# 4501-WB-AV-BMS-REV-A2-ISOSPI.net
KiCad netlist of a schematic drawn in Altium Designer
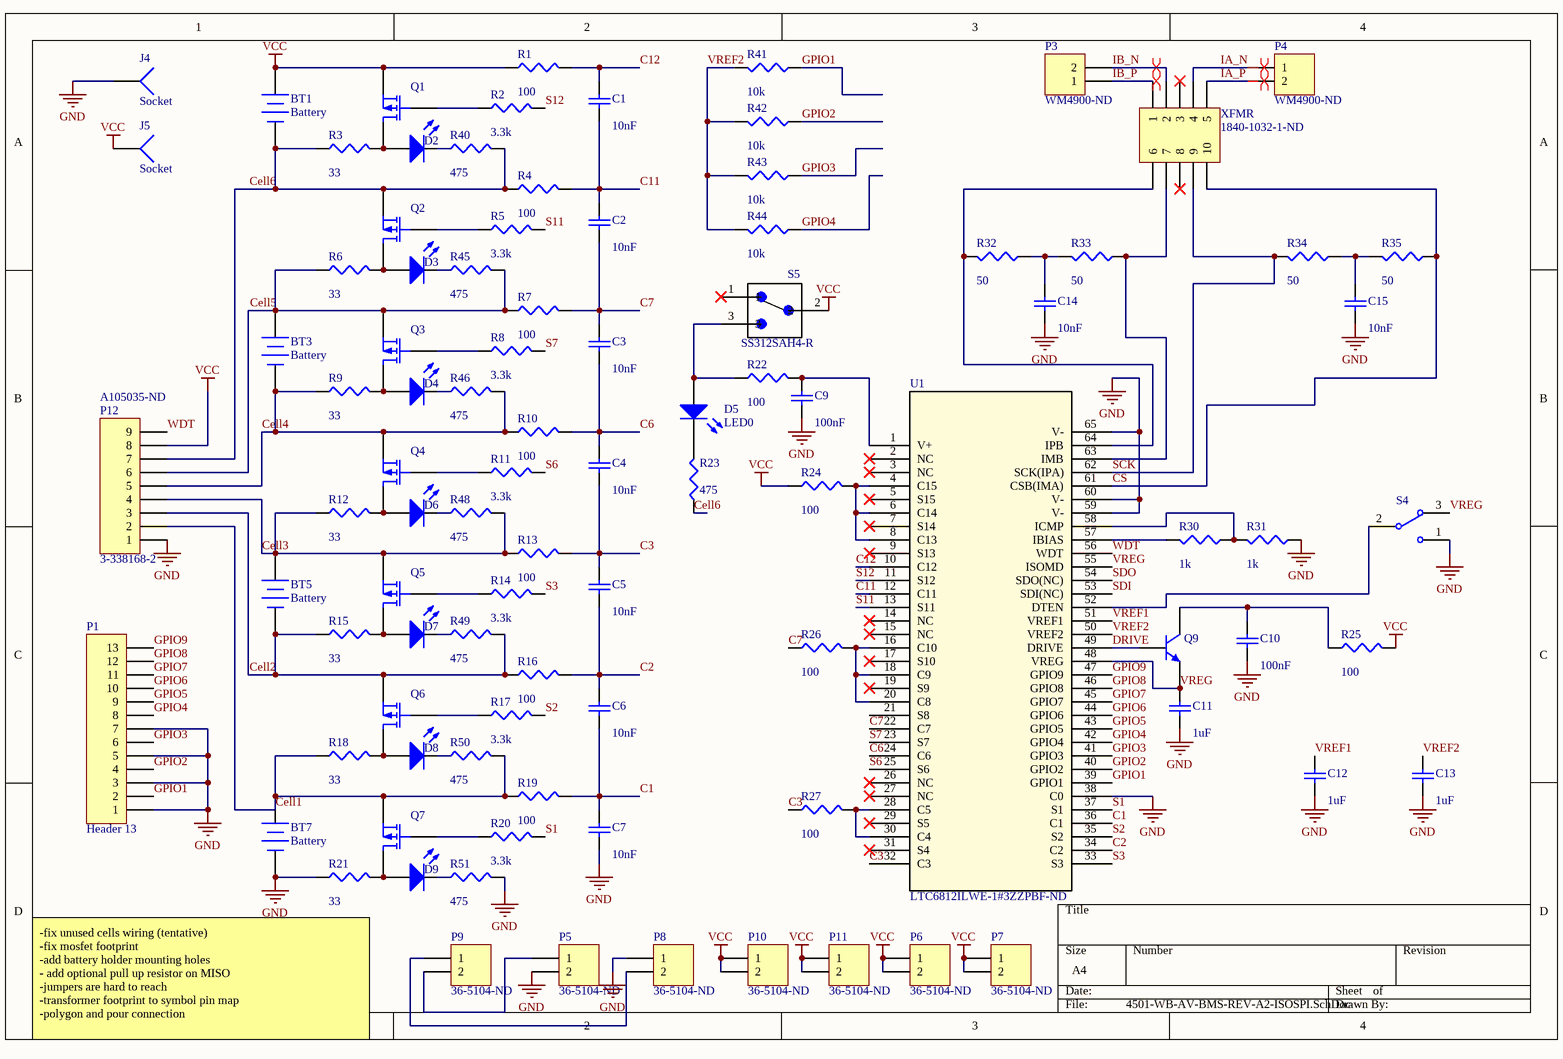
[diagram p0: 4501-WB-AV-BMS-REV-A2-ISOSPI.SchDoc]

(export (version "E")
  (design (tool "Eeschema 10.0.6"))
  (components
    (comp (ref "BT1")
      (value "Battery")
      (footprint "18650 SMD:PCBComponent_1")
      (description "Multicell Battery")
      (fields (field (name "PUBLISHER") "Altium Limited"))
      (libsource (lib "Miscellaneous Devices") (part "Battery"))
    )
    (comp (ref "BT3")
      (value "Battery")
      (footprint "18650 SMD:PCBComponent_1")
      (description "Multicell Battery")
      (fields (field (name "PUBLISHER") "Altium Limited"))
      (libsource (lib "Miscellaneous Devices") (part "Battery"))
    )
    (comp (ref "BT5")
      (value "Battery")
      (footprint "18650 SMD:PCBComponent_1")
      (description "Multicell Battery")
      (fields (field (name "PUBLISHER") "Altium Limited"))
      (libsource (lib "Miscellaneous Devices") (part "Battery"))
    )
    (comp (ref "BT7")
      (value "Battery")
      (footprint "18650 SMD:PCBComponent_1")
      (description "Multicell Battery")
      (fields (field (name "PUBLISHER") "Altium Limited"))
      (libsource (lib "Miscellaneous Devices") (part "Battery"))
    )
    (comp (ref "C1")
      (value "10nF")
      (footprint "1608[0603]")
      (description "Capacitor (Semiconductor SIM Model)")
      (fields (field (name "Comment") "399-1092-1-ND") (field (name "PUBLISHER") "Altium Limited"))
      (libsource (lib "Miscellaneous Devices") (part "Cap Semi"))
    )
    (comp (ref "C2")
      (value "10nF")
      (footprint "1608[0603]")
      (description "Capacitor (Semiconductor SIM Model)")
      (fields (field (name "Comment") "399-1092-1-ND") (field (name "PUBLISHER") "Altium Limited"))
      (libsource (lib "Miscellaneous Devices") (part "Cap Semi"))
    )
    (comp (ref "C3")
      (value "10nF")
      (footprint "1608[0603]")
      (description "Capacitor (Semiconductor SIM Model)")
      (fields (field (name "Comment") "399-1092-1-ND") (field (name "PUBLISHER") "Altium Limited"))
      (libsource (lib "Miscellaneous Devices") (part "Cap Semi"))
    )
    (comp (ref "C4")
      (value "10nF")
      (footprint "1608[0603]")
      (description "Capacitor (Semiconductor SIM Model)")
      (fields (field (name "Comment") "399-1092-1-ND") (field (name "PUBLISHER") "Altium Limited"))
      (libsource (lib "Miscellaneous Devices") (part "Cap Semi"))
    )
    (comp (ref "C5")
      (value "10nF")
      (footprint "1608[0603]")
      (description "Capacitor (Semiconductor SIM Model)")
      (fields (field (name "Comment") "399-1092-1-ND") (field (name "PUBLISHER") "Altium Limited"))
      (libsource (lib "Miscellaneous Devices") (part "Cap Semi"))
    )
    (comp (ref "C6")
      (value "10nF")
      (footprint "1608[0603]")
      (description "Capacitor (Semiconductor SIM Model)")
      (fields (field (name "Comment") "399-1092-1-ND") (field (name "PUBLISHER") "Altium Limited"))
      (libsource (lib "Miscellaneous Devices") (part "Cap Semi"))
    )
    (comp (ref "C7")
      (value "10nF")
      (footprint "1608[0603]")
      (description "Capacitor (Semiconductor SIM Model)")
      (fields (field (name "Comment") "399-1092-1-ND") (field (name "PUBLISHER") "Altium Limited"))
      (libsource (lib "Miscellaneous Devices") (part "Cap Semi"))
    )
    (comp (ref "C9")
      (value "100nF")
      (footprint "6-0805_N")
      (description "Capacitor (Semiconductor SIM Model)")
      (fields (field (name "Comment") "1276-1090-1-ND") (field (name "PUBLISHER") "Altium Limited"))
      (libsource (lib "Miscellaneous Devices") (part "Cap Semi"))
    )
    (comp (ref "C10")
      (value "100nF")
      (footprint "6-0805_N")
      (description "Capacitor (Semiconductor SIM Model)")
      (fields (field (name "Comment") "1276-1090-1-ND") (field (name "PUBLISHER") "Altium Limited"))
      (libsource (lib "Miscellaneous Devices") (part "Cap Semi"))
    )
    (comp (ref "C11")
      (value "1uF")
      (footprint "6-0805_N")
      (description "Capacitor (Semiconductor SIM Model)")
      (fields (field (name "Comment") "311-3498-1-ND") (field (name "PUBLISHER") "Altium Limited"))
      (libsource (lib "Miscellaneous Devices") (part "Cap Semi"))
    )
    (comp (ref "C12")
      (value "1uF")
      (footprint "6-0805_N")
      (description "Capacitor (Semiconductor SIM Model)")
      (fields (field (name "Comment") "311-3498-1-ND") (field (name "PUBLISHER") "Altium Limited"))
      (libsource (lib "Miscellaneous Devices") (part "Cap Semi"))
    )
    (comp (ref "C13")
      (value "1uF")
      (footprint "6-0805_N")
      (description "Capacitor (Semiconductor SIM Model)")
      (fields (field (name "Comment") "311-3498-1-ND") (field (name "PUBLISHER") "Altium Limited"))
      (libsource (lib "Miscellaneous Devices") (part "Cap Semi"))
    )
    (comp (ref "C14")
      (value "10nF")
      (footprint "1608[0603]")
      (description "Capacitor (Semiconductor SIM Model)")
      (fields (field (name "Comment") "399-1092-1-ND") (field (name "PUBLISHER") "Altium Limited"))
      (libsource (lib "Miscellaneous Devices") (part "Cap Semi"))
    )
    (comp (ref "C15")
      (value "10nF")
      (footprint "1608[0603]")
      (description "Capacitor (Semiconductor SIM Model)")
      (fields (field (name "Comment") "399-1092-1-ND") (field (name "PUBLISHER") "Altium Limited"))
      (libsource (lib "Miscellaneous Devices") (part "Cap Semi"))
    )
    (comp (ref "D2")
      (value "160-1435-1-ND")
      (footprint "J1-0603")
      (description "Typical INFRARED GaAs LED")
      (fields (field (name "PUBLISHER") "Altium Limited"))
      (libsource (lib "Miscellaneous Devices") (part "LED0"))
    )
    (comp (ref "D3")
      (value "160-1435-1-ND")
      (footprint "J1-0603")
      (description "Typical INFRARED GaAs LED")
      (fields (field (name "PUBLISHER") "Altium Limited"))
      (libsource (lib "Miscellaneous Devices") (part "LED0"))
    )
    (comp (ref "D4")
      (value "160-1435-1-ND")
      (footprint "J1-0603")
      (description "Typical INFRARED GaAs LED")
      (fields (field (name "PUBLISHER") "Altium Limited"))
      (libsource (lib "Miscellaneous Devices") (part "LED0"))
    )
    (comp (ref "D5")
      (value "LED0")
      (footprint "J1-0603")
      (description "Typical INFRARED GaAs LED")
      (fields (field (name "PUBLISHER") "Altium Limited"))
      (libsource (lib "Miscellaneous Devices") (part "LED0"))
    )
    (comp (ref "D6")
      (value "160-1435-1-ND")
      (footprint "J1-0603")
      (description "Typical INFRARED GaAs LED")
      (fields (field (name "PUBLISHER") "Altium Limited"))
      (libsource (lib "Miscellaneous Devices") (part "LED0"))
    )
    (comp (ref "D7")
      (value "160-1435-1-ND")
      (footprint "J1-0603")
      (description "Typical INFRARED GaAs LED")
      (fields (field (name "PUBLISHER") "Altium Limited"))
      (libsource (lib "Miscellaneous Devices") (part "LED0"))
    )
    (comp (ref "D8")
      (value "160-1435-1-ND")
      (footprint "J1-0603")
      (description "Typical INFRARED GaAs LED")
      (fields (field (name "PUBLISHER") "Altium Limited"))
      (libsource (lib "Miscellaneous Devices") (part "LED0"))
    )
    (comp (ref "D9")
      (value "160-1435-1-ND")
      (footprint "J1-0603")
      (description "Typical INFRARED GaAs LED")
      (fields (field (name "PUBLISHER") "Altium Limited"))
      (libsource (lib "Miscellaneous Devices") (part "LED0"))
    )
    (comp (ref "J4")
      (value "Socket")
      (footprint "SMD Power Pad:PCBComponent_1")
      (fields (field (name "PUBLISHER") "Altium Limited"))
      (libsource (lib "Miscellaneous Connectors") (part "Socket"))
    )
    (comp (ref "J5")
      (value "Socket")
      (footprint "SMD Power Pad:PCBComponent_1")
      (fields (field (name "PUBLISHER") "Altium Limited"))
      (libsource (lib "Miscellaneous Connectors") (part "Socket"))
    )
    (comp (ref "P1")
      (value "Header 13")
      (footprint "DIP10")
      (description "Header, 13-Pin")
      (fields (field (name "PUBLISHER") "Altium Limited"))
      (libsource (lib "Miscellaneous Connectors") (part "Header 13"))
    )
    (comp (ref "P3")
      (value "WM4900-ND")
      (footprint "Molex Connectors:WM4900-ND")
      (description "Header, 2-Pin")
      (fields (field (name "PUBLISHER") "Altium Limited"))
      (libsource (lib "Miscellaneous Connectors") (part "Header 2"))
    )
    (comp (ref "P4")
      (value "WM4900-ND")
      (footprint "Molex Connectors:WM4900-ND")
      (description "Header, 2-Pin")
      (fields (field (name "PUBLISHER") "Altium Limited"))
      (libsource (lib "") (part "Header 2_1"))
    )
    (comp (ref "P5")
      (value "36-5104-ND")
      (footprint "5104:PCBComponent_1")
      (description "Header, 2-Pin")
      (fields (field (name "PUBLISHER") "Altium Limited"))
      (libsource (lib "") (part "Header 2_1"))
    )
    (comp (ref "P6")
      (value "36-5104-ND")
      (footprint "5104:PCBComponent_1")
      (description "Header, 2-Pin")
      (fields (field (name "PUBLISHER") "Altium Limited"))
      (libsource (lib "") (part "Header 2_1"))
    )
    (comp (ref "P7")
      (value "36-5104-ND")
      (footprint "5104:PCBComponent_1")
      (description "Header, 2-Pin")
      (fields (field (name "PUBLISHER") "Altium Limited"))
      (libsource (lib "") (part "Header 2_1"))
    )
    (comp (ref "P8")
      (value "36-5104-ND")
      (footprint "5104:PCBComponent_1")
      (description "Header, 2-Pin")
      (fields (field (name "PUBLISHER") "Altium Limited"))
      (libsource (lib "") (part "Header 2_1"))
    )
    (comp (ref "P9")
      (value "36-5104-ND")
      (footprint "5104:PCBComponent_1")
      (description "Header, 2-Pin")
      (fields (field (name "PUBLISHER") "Altium Limited"))
      (libsource (lib "") (part "Header 2_1"))
    )
    (comp (ref "P10")
      (value "36-5104-ND")
      (footprint "5104:PCBComponent_1")
      (description "Header, 2-Pin")
      (fields (field (name "PUBLISHER") "Altium Limited"))
      (libsource (lib "") (part "Header 2_1"))
    )
    (comp (ref "P11")
      (value "36-5104-ND")
      (footprint "5104:PCBComponent_1")
      (description "Header, 2-Pin")
      (fields (field (name "PUBLISHER") "Altium Limited"))
      (libsource (lib "") (part "Header 2_1"))
    )
    (comp (ref "P12")
      (value "3-338168-2")
      (footprint "CONN_3-338168-2")
      (description "Header, 9-Pin")
      (fields
        (field (name "SUPPLIER PART NUMBER 1") "A105035-ND")
        (field (name "PUBLISHER") "Altium Limited")
      )
      (libsource (lib "Miscellaneous Connectors") (part "Header 9"))
    )
    (comp (ref "Q1")
      (value "BSS308PEH6327XTSA1CT-ND")
      (footprint "SOT95P245X110-3N")
      (description "P-Channel MOSFET")
      (fields (field (name "PUBLISHER") "Altium Limited"))
      (libsource (lib "Miscellaneous Devices") (part "MOSFET-P"))
    )
    (comp (ref "Q2")
      (value "BSS308PEH6327XTSA1CT-ND")
      (footprint "SOT95P245X110-3N")
      (description "P-Channel MOSFET")
      (fields (field (name "PUBLISHER") "Altium Limited"))
      (libsource (lib "Miscellaneous Devices") (part "MOSFET-P"))
    )
    (comp (ref "Q3")
      (value "BSS308PEH6327XTSA1CT-ND")
      (footprint "SOT95P245X110-3N")
      (description "P-Channel MOSFET")
      (fields (field (name "PUBLISHER") "Altium Limited"))
      (libsource (lib "Miscellaneous Devices") (part "MOSFET-P"))
    )
    (comp (ref "Q4")
      (value "BSS308PEH6327XTSA1CT-ND")
      (footprint "SOT95P245X110-3N")
      (description "P-Channel MOSFET")
      (fields (field (name "PUBLISHER") "Altium Limited"))
      (libsource (lib "Miscellaneous Devices") (part "MOSFET-P"))
    )
    (comp (ref "Q5")
      (value "BSS308PEH6327XTSA1CT-ND")
      (footprint "SOT95P245X110-3N")
      (description "P-Channel MOSFET")
      (fields (field (name "PUBLISHER") "Altium Limited"))
      (libsource (lib "Miscellaneous Devices") (part "MOSFET-P"))
    )
    (comp (ref "Q6")
      (value "BSS308PEH6327XTSA1CT-ND")
      (footprint "SOT95P245X110-3N")
      (description "P-Channel MOSFET")
      (fields (field (name "PUBLISHER") "Altium Limited"))
      (libsource (lib "Miscellaneous Devices") (part "MOSFET-P"))
    )
    (comp (ref "Q7")
      (value "BSS308PEH6327XTSA1CT-ND")
      (footprint "SOT95P245X110-3N")
      (description "P-Channel MOSFET")
      (fields (field (name "PUBLISHER") "Altium Limited"))
      (libsource (lib "Miscellaneous Devices") (part "MOSFET-P"))
    )
    (comp (ref "Q9")
      (value "DXT5551P5-13CT-ND")
      (footprint "DXT5551P5-13")
      (description "NPN General Purpose Amplifier")
      (fields (field (name "PUBLISHER") "Altium Limited"))
      (libsource (lib "Miscellaneous Devices") (part "2N3904"))
    )
    (comp (ref "R1")
      (value "100")
      (footprint "J1-0603")
      (description "Resistor")
      (fields (field (name "Comment") "A129676CT-ND") (field (name "PUBLISHER") "Altium Limited"))
      (libsource (lib "Miscellaneous Devices") (part "Res3"))
    )
    (comp (ref "R2")
      (value "3.3k")
      (footprint "J1-0603")
      (description "Resistor")
      (fields (field (name "Comment") "A129543CT-ND") (field (name "PUBLISHER") "Altium Limited"))
      (libsource (lib "Miscellaneous Devices") (part "Res3"))
    )
    (comp (ref "R3")
      (value "33")
      (footprint "12Z-2010")
      (description "Resistor")
      (fields (field (name "Comment") "A130642CT-ND") (field (name "PUBLISHER") "Altium Limited"))
      (libsource (lib "Miscellaneous Devices") (part "Res3"))
    )
    (comp (ref "R4")
      (value "100")
      (footprint "J1-0603")
      (description "Resistor")
      (fields (field (name "Comment") "A129676CT-ND") (field (name "PUBLISHER") "Altium Limited"))
      (libsource (lib "Miscellaneous Devices") (part "Res3"))
    )
    (comp (ref "R5")
      (value "3.3k")
      (footprint "J1-0603")
      (description "Resistor")
      (fields (field (name "Comment") "A129543CT-ND") (field (name "PUBLISHER") "Altium Limited"))
      (libsource (lib "Miscellaneous Devices") (part "Res3"))
    )
    (comp (ref "R6")
      (value "33")
      (footprint "12Z-2010")
      (description "Resistor")
      (fields (field (name "Comment") "A130642CT-ND") (field (name "PUBLISHER") "Altium Limited"))
      (libsource (lib "Miscellaneous Devices") (part "Res3"))
    )
    (comp (ref "R7")
      (value "100")
      (footprint "J1-0603")
      (description "Resistor")
      (fields (field (name "Comment") "A129676CT-ND") (field (name "PUBLISHER") "Altium Limited"))
      (libsource (lib "Miscellaneous Devices") (part "Res3"))
    )
    (comp (ref "R8")
      (value "3.3k")
      (footprint "J1-0603")
      (description "Resistor")
      (fields (field (name "Comment") "A129543CT-ND") (field (name "PUBLISHER") "Altium Limited"))
      (libsource (lib "Miscellaneous Devices") (part "Res3"))
    )
    (comp (ref "R9")
      (value "33")
      (footprint "12Z-2010")
      (description "Resistor")
      (fields (field (name "Comment") "A130642CT-ND") (field (name "PUBLISHER") "Altium Limited"))
      (libsource (lib "Miscellaneous Devices") (part "Res3"))
    )
    (comp (ref "R10")
      (value "100")
      (footprint "J1-0603")
      (description "Resistor")
      (fields (field (name "Comment") "A129676CT-ND") (field (name "PUBLISHER") "Altium Limited"))
      (libsource (lib "Miscellaneous Devices") (part "Res3"))
    )
    (comp (ref "R11")
      (value "3.3k")
      (footprint "J1-0603")
      (description "Resistor")
      (fields (field (name "Comment") "A129543CT-ND") (field (name "PUBLISHER") "Altium Limited"))
      (libsource (lib "Miscellaneous Devices") (part "Res3"))
    )
    (comp (ref "R12")
      (value "33")
      (footprint "12Z-2010")
      (description "Resistor")
      (fields (field (name "Comment") "A130642CT-ND") (field (name "PUBLISHER") "Altium Limited"))
      (libsource (lib "Miscellaneous Devices") (part "Res3"))
    )
    (comp (ref "R13")
      (value "100")
      (footprint "J1-0603")
      (description "Resistor")
      (fields (field (name "Comment") "A129676CT-ND") (field (name "PUBLISHER") "Altium Limited"))
      (libsource (lib "Miscellaneous Devices") (part "Res3"))
    )
    (comp (ref "R14")
      (value "3.3k")
      (footprint "J1-0603")
      (description "Resistor")
      (fields (field (name "Comment") "A129543CT-ND") (field (name "PUBLISHER") "Altium Limited"))
      (libsource (lib "Miscellaneous Devices") (part "Res3"))
    )
    (comp (ref "R15")
      (value "33")
      (footprint "12Z-2010")
      (description "Resistor")
      (fields (field (name "Comment") "A130642CT-ND") (field (name "PUBLISHER") "Altium Limited"))
      (libsource (lib "Miscellaneous Devices") (part "Res3"))
    )
    (comp (ref "R16")
      (value "100")
      (footprint "J1-0603")
      (description "Resistor")
      (fields (field (name "Comment") "A129676CT-ND") (field (name "PUBLISHER") "Altium Limited"))
      (libsource (lib "Miscellaneous Devices") (part "Res3"))
    )
    (comp (ref "R17")
      (value "3.3k")
      (footprint "J1-0603")
      (description "Resistor")
      (fields (field (name "Comment") "A129543CT-ND") (field (name "PUBLISHER") "Altium Limited"))
      (libsource (lib "Miscellaneous Devices") (part "Res3"))
    )
    (comp (ref "R18")
      (value "33")
      (footprint "12Z-2010")
      (description "Resistor")
      (fields (field (name "Comment") "A130642CT-ND") (field (name "PUBLISHER") "Altium Limited"))
      (libsource (lib "Miscellaneous Devices") (part "Res3"))
    )
    (comp (ref "R19")
      (value "100")
      (footprint "J1-0603")
      (description "Resistor")
      (fields (field (name "Comment") "A129676CT-ND") (field (name "PUBLISHER") "Altium Limited"))
      (libsource (lib "Miscellaneous Devices") (part "Res3"))
    )
    (comp (ref "R20")
      (value "3.3k")
      (footprint "J1-0603")
      (description "Resistor")
      (fields (field (name "Comment") "A129543CT-ND") (field (name "PUBLISHER") "Altium Limited"))
      (libsource (lib "Miscellaneous Devices") (part "Res3"))
    )
    (comp (ref "R21")
      (value "33")
      (footprint "12Z-2010")
      (description "Resistor")
      (fields (field (name "Comment") "A130642CT-ND") (field (name "PUBLISHER") "Altium Limited"))
      (libsource (lib "Miscellaneous Devices") (part "Res3"))
    )
    (comp (ref "R22")
      (value "100")
      (footprint "J1-0603")
      (description "Resistor")
      (fields (field (name "Comment") "A129676CT-ND") (field (name "PUBLISHER") "Altium Limited"))
      (libsource (lib "Miscellaneous Devices") (part "Res3"))
    )
    (comp (ref "R23")
      (value "475")
      (footprint "J1-0603")
      (description "Resistor")
      (fields (field (name "Comment") "RMCF2010JT33R0CT-ND") (field (name "PUBLISHER") "Altium Limited"))
      (libsource (lib "Miscellaneous Devices") (part "Res3"))
    )
    (comp (ref "R24")
      (value "100")
      (footprint "J1-0603")
      (description "Resistor")
      (fields (field (name "Comment") "A129676CT-ND") (field (name "PUBLISHER") "Altium Limited"))
      (libsource (lib "Miscellaneous Devices") (part "Res3"))
    )
    (comp (ref "R25")
      (value "100")
      (footprint "J1-0603")
      (description "Resistor")
      (fields (field (name "Comment") "A129676CT-ND") (field (name "PUBLISHER") "Altium Limited"))
      (libsource (lib "Miscellaneous Devices") (part "Res3"))
    )
    (comp (ref "R26")
      (value "100")
      (footprint "J1-0603")
      (description "Resistor")
      (fields (field (name "Comment") "A129676CT-ND") (field (name "PUBLISHER") "Altium Limited"))
      (libsource (lib "Miscellaneous Devices") (part "Res3"))
    )
    (comp (ref "R27")
      (value "100")
      (footprint "J1-0603")
      (description "Resistor")
      (fields (field (name "Comment") "A129676CT-ND") (field (name "PUBLISHER") "Altium Limited"))
      (libsource (lib "Miscellaneous Devices") (part "Res3"))
    )
    (comp (ref "R30")
      (value "1k")
      (footprint "J1-0603")
      (description "Resistor")
      (fields (field (name "Comment") "RNCP0603FTD1K00CT-ND") (field (name "PUBLISHER") "Altium Limited"))
      (libsource (lib "Miscellaneous Devices") (part "Res3"))
    )
    (comp (ref "R31")
      (value "1k")
      (footprint "J1-0603")
      (description "Resistor")
      (fields (field (name "Comment") "RNCP0603FTD1K00CT-ND") (field (name "PUBLISHER") "Altium Limited"))
      (libsource (lib "Miscellaneous Devices") (part "Res3"))
    )
    (comp (ref "R32")
      (value "50")
      (footprint "J1-0603")
      (description "Resistor")
      (fields (field (name "Comment") "311-2598-1-ND") (field (name "PUBLISHER") "Altium Limited"))
      (libsource (lib "Miscellaneous Devices") (part "Res3"))
    )
    (comp (ref "R33")
      (value "50")
      (footprint "J1-0603")
      (description "Resistor")
      (fields (field (name "Comment") "311-2598-1-ND") (field (name "PUBLISHER") "Altium Limited"))
      (libsource (lib "Miscellaneous Devices") (part "Res3"))
    )
    (comp (ref "R34")
      (value "50")
      (footprint "J1-0603")
      (description "Resistor")
      (fields (field (name "Comment") "311-2598-1-ND") (field (name "PUBLISHER") "Altium Limited"))
      (libsource (lib "Miscellaneous Devices") (part "Res3"))
    )
    (comp (ref "R35")
      (value "50")
      (footprint "J1-0603")
      (description "Resistor")
      (fields (field (name "Comment") "311-2598-1-ND") (field (name "PUBLISHER") "Altium Limited"))
      (libsource (lib "Miscellaneous Devices") (part "Res3"))
    )
    (comp (ref "R40")
      (value "475")
      (footprint "J1-0603")
      (description "Resistor")
      (fields (field (name "Comment") "RMCF2010JT33R0CT-ND") (field (name "PUBLISHER") "Altium Limited"))
      (libsource (lib "Miscellaneous Devices") (part "Res3"))
    )
    (comp (ref "R41")
      (value "10k")
      (footprint "J1-0603")
      (description "Resistor")
      (fields (field (name "Comment") "RNCP0603FTD10K0CT-ND") (field (name "PUBLISHER") "Altium Limited"))
      (libsource (lib "Miscellaneous Devices") (part "Res3"))
    )
    (comp (ref "R42")
      (value "10k")
      (footprint "J1-0603")
      (description "Resistor")
      (fields (field (name "Comment") "RNCP0603FTD10K0CT-ND") (field (name "PUBLISHER") "Altium Limited"))
      (libsource (lib "Miscellaneous Devices") (part "Res3"))
    )
    (comp (ref "R43")
      (value "10k")
      (footprint "J1-0603")
      (description "Resistor")
      (fields (field (name "Comment") "RNCP0603FTD10K0CT-ND") (field (name "PUBLISHER") "Altium Limited"))
      (libsource (lib "Miscellaneous Devices") (part "Res3"))
    )
    (comp (ref "R44")
      (value "10k")
      (footprint "J1-0603")
      (description "Resistor")
      (fields (field (name "Comment") "RNCP0603FTD10K0CT-ND") (field (name "PUBLISHER") "Altium Limited"))
      (libsource (lib "Miscellaneous Devices") (part "Res3"))
    )
    (comp (ref "R45")
      (value "475")
      (footprint "J1-0603")
      (description "Resistor")
      (fields (field (name "Comment") "RMCF2010JT33R0CT-ND") (field (name "PUBLISHER") "Altium Limited"))
      (libsource (lib "Miscellaneous Devices") (part "Res3"))
    )
    (comp (ref "R46")
      (value "475")
      (footprint "J1-0603")
      (description "Resistor")
      (fields (field (name "Comment") "RMCF2010JT33R0CT-ND") (field (name "PUBLISHER") "Altium Limited"))
      (libsource (lib "Miscellaneous Devices") (part "Res3"))
    )
    (comp (ref "R48")
      (value "475")
      (footprint "J1-0603")
      (description "Resistor")
      (fields (field (name "Comment") "RMCF2010JT33R0CT-ND") (field (name "PUBLISHER") "Altium Limited"))
      (libsource (lib "Miscellaneous Devices") (part "Res3"))
    )
    (comp (ref "R49")
      (value "475")
      (footprint "J1-0603")
      (description "Resistor")
      (fields (field (name "Comment") "RMCF2010JT33R0CT-ND") (field (name "PUBLISHER") "Altium Limited"))
      (libsource (lib "Miscellaneous Devices") (part "Res3"))
    )
    (comp (ref "R50")
      (value "475")
      (footprint "J1-0603")
      (description "Resistor")
      (fields (field (name "Comment") "RMCF2010JT33R0CT-ND") (field (name "PUBLISHER") "Altium Limited"))
      (libsource (lib "Miscellaneous Devices") (part "Res3"))
    )
    (comp (ref "R51")
      (value "475")
      (footprint "J1-0603")
      (description "Resistor")
      (fields (field (name "Comment") "RMCF2010JT33R0CT-ND") (field (name "PUBLISHER") "Altium Limited"))
      (libsource (lib "Miscellaneous Devices") (part "Res3"))
    )
    (comp (ref "S4")
      (value "S9337-ND, SAM8981-ND")
      (footprint "*TSM-103-01-L-SV")
      (description "SPDT Subminiature Toggle Switch, Right Angle Mounting, Vertical Actuation")
      (fields (field (name "PUBLISHER") "Altium Limited"))
      (libsource (lib "Miscellaneous Devices") (part "SW-SPDT"))
    )
    (comp (ref "S5")
      (value "SS312SAH4-R")
      (footprint "*SW_SS312SAH4-R")
      (description "Switch Slide ON None ON SPDT Side Slide 0.1A 28VAC 28VDC 0.4VA 10000Cycles Gull Wing SMD T/R")
      (fields (field (name "MF") "NKK Switches"))
      (libsource (lib "SS312SAH4-R") (part "SS312SAH4-R"))
    )
    (comp (ref "U1")
      (value "LTC6812ILWE-1#3ZZPBF-ND")
      (footprint "LQFP64_LWE_A - duplicate")
      (description "No Description Available")
      (fields (field (name "COPYRIGHT") "Copyright (C) 2018 Accelerated Designs. All rights reserved"))
      (libsource (lib "LTC6812") (part "LTC6812HLWE-1"))
    )
    (comp (ref "XFMR")
      (value "1840-1032-1-ND")
      (footprint "HM2100NLT")
      (description "Header, 5-Pin, Dual row\r\nHM2100NLT")
      (fields (field (name "PUBLISHER") "Altium Limited"))
      (libsource (lib "Miscellaneous Connectors") (part "Header 5X2A"))
    )
  )
  (nets
    (net (code "1") (name "/C1") (class "Default")
      (node (ref "C6") (pin "1") (pinfunction "1_1") (pintype "passive"))
      (node (ref "C7") (pin "2") (pinfunction "2_2") (pintype "passive"))
      (node (ref "R19") (pin "2") (pinfunction "2_2") (pintype "passive"))
      (node (ref "U1") (pin "36") (pinfunction "C1_36") (pintype "passive"))
    )
    (net (code "2") (name "/C2") (class "Default")
      (node (ref "C5") (pin "1") (pinfunction "1_1") (pintype "passive"))
      (node (ref "C6") (pin "2") (pinfunction "2_2") (pintype "passive"))
      (node (ref "R16") (pin "2") (pinfunction "2_2") (pintype "passive"))
      (node (ref "U1") (pin "34") (pinfunction "C2_34") (pintype "passive"))
    )
    (net (code "3") (name "/C3") (class "Default")
      (node (ref "C4") (pin "1") (pinfunction "1_1") (pintype "passive"))
      (node (ref "C5") (pin "2") (pinfunction "2_2") (pintype "passive"))
      (node (ref "R13") (pin "2") (pinfunction "2_2") (pintype "passive"))
      (node (ref "R27") (pin "1") (pinfunction "1_1") (pintype "passive"))
      (node (ref "U1") (pin "32") (pinfunction "C3_32") (pintype "passive"))
    )
    (net (code "4") (name "/C6") (class "Default")
      (node (ref "C3") (pin "1") (pinfunction "1_1") (pintype "passive"))
      (node (ref "C4") (pin "2") (pinfunction "2_2") (pintype "passive"))
      (node (ref "R10") (pin "2") (pinfunction "2_2") (pintype "passive"))
      (node (ref "U1") (pin "24") (pinfunction "C6_24") (pintype "passive"))
    )
    (net (code "5") (name "/C7") (class "Default")
      (node (ref "C2") (pin "1") (pinfunction "1_1") (pintype "passive"))
      (node (ref "C3") (pin "2") (pinfunction "2_2") (pintype "passive"))
      (node (ref "R26") (pin "1") (pinfunction "1_1") (pintype "passive"))
      (node (ref "R7") (pin "2") (pinfunction "2_2") (pintype "passive"))
      (node (ref "U1") (pin "22") (pinfunction "C7_22") (pintype "passive"))
    )
    (net (code "6") (name "/C11") (class "Default")
      (node (ref "C1") (pin "1") (pinfunction "1_1") (pintype "passive"))
      (node (ref "C2") (pin "2") (pinfunction "2_2") (pintype "passive"))
      (node (ref "R4") (pin "2") (pinfunction "2_2") (pintype "passive"))
      (node (ref "U1") (pin "12") (pinfunction "C11_12") (pintype "passive"))
    )
    (net (code "7") (name "/C12") (class "Default")
      (node (ref "C1") (pin "2") (pinfunction "2_2") (pintype "passive"))
      (node (ref "R1") (pin "2") (pinfunction "2_2") (pintype "passive"))
      (node (ref "U1") (pin "10") (pinfunction "C12_10") (pintype "passive"))
    )
    (net (code "8") (name "/CS") (class "Default")
      (node (ref "R35") (pin "2") (pinfunction "2_2") (pintype "passive"))
      (node (ref "U1") (pin "61") (pinfunction "CSB(IMA)_61") (pintype "passive"))
      (node (ref "XFMR") (pin "10") (pinfunction "10_10") (pintype "passive"))
    )
    (net (code "9") (name "/Cell1") (class "Default")
      (node (ref "BT7") (pin "1") (pinfunction "+_1") (pintype "passive"))
      (node (ref "P12") (pin "2") (pinfunction "2_2") (pintype "passive"))
      (node (ref "Q7") (pin "3") (pinfunction "S_3") (pintype "passive"))
      (node (ref "R18") (pin "2") (pinfunction "2_2") (pintype "passive"))
      (node (ref "R19") (pin "1") (pinfunction "1_1") (pintype "passive"))
      (node (ref "R50") (pin "1") (pinfunction "1_1") (pintype "passive"))
    )
    (net (code "10") (name "/Cell2") (class "Default")
      (node (ref "BT5") (pin "2") (pinfunction "-_2") (pintype "passive"))
      (node (ref "P12") (pin "3") (pinfunction "3_3") (pintype "passive"))
      (node (ref "Q6") (pin "3") (pinfunction "S_3") (pintype "passive"))
      (node (ref "R15") (pin "2") (pinfunction "2_2") (pintype "passive"))
      (node (ref "R16") (pin "1") (pinfunction "1_1") (pintype "passive"))
      (node (ref "R49") (pin "1") (pinfunction "1_1") (pintype "passive"))
    )
    (net (code "11") (name "/Cell3") (class "Default")
      (node (ref "BT5") (pin "1") (pinfunction "+_1") (pintype "passive"))
      (node (ref "P12") (pin "4") (pinfunction "4_4") (pintype "passive"))
      (node (ref "Q5") (pin "3") (pinfunction "S_3") (pintype "passive"))
      (node (ref "R12") (pin "2") (pinfunction "2_2") (pintype "passive"))
      (node (ref "R13") (pin "1") (pinfunction "1_1") (pintype "passive"))
      (node (ref "R48") (pin "1") (pinfunction "1_1") (pintype "passive"))
    )
    (net (code "12") (name "/Cell4") (class "Default")
      (node (ref "BT3") (pin "2") (pinfunction "-_2") (pintype "passive"))
      (node (ref "P12") (pin "5") (pinfunction "5_5") (pintype "passive"))
      (node (ref "Q4") (pin "3") (pinfunction "S_3") (pintype "passive"))
      (node (ref "R10") (pin "1") (pinfunction "1_1") (pintype "passive"))
      (node (ref "R46") (pin "1") (pinfunction "1_1") (pintype "passive"))
      (node (ref "R9") (pin "2") (pinfunction "2_2") (pintype "passive"))
    )
    (net (code "13") (name "/Cell5") (class "Default")
      (node (ref "BT3") (pin "1") (pinfunction "+_1") (pintype "passive"))
      (node (ref "P12") (pin "6") (pinfunction "6_6") (pintype "passive"))
      (node (ref "Q3") (pin "3") (pinfunction "S_3") (pintype "passive"))
      (node (ref "R45") (pin "1") (pinfunction "1_1") (pintype "passive"))
      (node (ref "R6") (pin "2") (pinfunction "2_2") (pintype "passive"))
      (node (ref "R7") (pin "1") (pinfunction "1_1") (pintype "passive"))
    )
    (net (code "14") (name "/Cell6") (class "Default")
      (node (ref "BT1") (pin "2") (pinfunction "-_2") (pintype "passive"))
      (node (ref "P12") (pin "7") (pinfunction "7_7") (pintype "passive"))
      (node (ref "Q2") (pin "3") (pinfunction "S_3") (pintype "passive"))
      (node (ref "R23") (pin "2") (pinfunction "2_2") (pintype "passive"))
      (node (ref "R3") (pin "2") (pinfunction "2_2") (pintype "passive"))
      (node (ref "R4") (pin "1") (pinfunction "1_1") (pintype "passive"))
      (node (ref "R40") (pin "1") (pinfunction "1_1") (pintype "passive"))
    )
    (net (code "15") (name "/DRIVE") (class "Default")
      (node (ref "Q9") (pin "2") (pinfunction "B_2") (pintype "passive"))
      (node (ref "U1") (pin "49") (pinfunction "DRIVE_49") (pintype "passive"))
    )
    (net (code "16") (name "/GPIO1") (class "Default")
      (node (ref "P1") (pin "2") (pinfunction "2_2") (pintype "passive"))
      (node (ref "R41") (pin "2") (pinfunction "2_2") (pintype "passive"))
      (node (ref "U1") (pin "39") (pinfunction "GPIO1_39") (pintype "passive"))
    )
    (net (code "17") (name "/GPIO2") (class "Default")
      (node (ref "P1") (pin "4") (pinfunction "4_4") (pintype "passive"))
      (node (ref "R42") (pin "2") (pinfunction "2_2") (pintype "passive"))
      (node (ref "U1") (pin "40") (pinfunction "GPIO2_40") (pintype "passive"))
    )
    (net (code "18") (name "/GPIO3") (class "Default")
      (node (ref "P1") (pin "6") (pinfunction "6_6") (pintype "passive"))
      (node (ref "R43") (pin "2") (pinfunction "2_2") (pintype "passive"))
      (node (ref "U1") (pin "41") (pinfunction "GPIO3_41") (pintype "passive"))
    )
    (net (code "19") (name "/GPIO4") (class "Default")
      (node (ref "P1") (pin "8") (pinfunction "8_8") (pintype "passive"))
      (node (ref "R44") (pin "2") (pinfunction "2_2") (pintype "passive"))
      (node (ref "U1") (pin "42") (pinfunction "GPIO4_42") (pintype "passive"))
    )
    (net (code "20") (name "/GPIO5") (class "Default")
      (node (ref "P1") (pin "9") (pinfunction "9_9") (pintype "passive"))
      (node (ref "U1") (pin "43") (pinfunction "GPIO5_43") (pintype "passive"))
    )
    (net (code "21") (name "/GPIO6") (class "Default")
      (node (ref "P1") (pin "10") (pinfunction "10_10") (pintype "passive"))
      (node (ref "U1") (pin "44") (pinfunction "GPIO6_44") (pintype "passive"))
    )
    (net (code "22") (name "/GPIO7") (class "Default")
      (node (ref "P1") (pin "11") (pinfunction "11_11") (pintype "passive"))
      (node (ref "U1") (pin "45") (pinfunction "GPIO7_45") (pintype "passive"))
    )
    (net (code "23") (name "/GPIO8") (class "Default")
      (node (ref "P1") (pin "12") (pinfunction "12_12") (pintype "passive"))
      (node (ref "U1") (pin "46") (pinfunction "GPIO8_46") (pintype "passive"))
    )
    (net (code "24") (name "/GPIO9") (class "Default")
      (node (ref "P1") (pin "13") (pinfunction "13_13") (pintype "passive"))
      (node (ref "U1") (pin "47") (pinfunction "GPIO9_47") (pintype "passive"))
    )
    (net (code "25") (name "/IA_N") (class "Default")
      (node (ref "P4") (pin "1") (pinfunction "1_1") (pintype "passive"))
      (node (ref "XFMR") (pin "4") (pinfunction "4_4") (pintype "passive"))
    )
    (net (code "26") (name "/IA_P") (class "Default")
      (node (ref "P4") (pin "2") (pinfunction "2_2") (pintype "passive"))
      (node (ref "XFMR") (pin "5") (pinfunction "5_5") (pintype "passive"))
    )
    (net (code "27") (name "/IB_N") (class "Default")
      (node (ref "P3") (pin "2") (pinfunction "2_2") (pintype "passive"))
      (node (ref "XFMR") (pin "2") (pinfunction "2_2") (pintype "passive"))
    )
    (net (code "28") (name "/IB_P") (class "Default")
      (node (ref "P3") (pin "1") (pinfunction "1_1") (pintype "passive"))
      (node (ref "XFMR") (pin "1") (pinfunction "1_1") (pintype "passive"))
    )
    (net (code "29") (name "/S1") (class "Default")
      (node (ref "R20") (pin "2") (pinfunction "2_2") (pintype "passive"))
      (node (ref "U1") (pin "37") (pinfunction "S1_37") (pintype "passive"))
    )
    (net (code "30") (name "/S2") (class "Default")
      (node (ref "R17") (pin "2") (pinfunction "2_2") (pintype "passive"))
      (node (ref "U1") (pin "35") (pinfunction "S2_35") (pintype "passive"))
    )
    (net (code "31") (name "/S3") (class "Default")
      (node (ref "R14") (pin "2") (pinfunction "2_2") (pintype "passive"))
      (node (ref "U1") (pin "33") (pinfunction "S3_33") (pintype "passive"))
    )
    (net (code "32") (name "/S6") (class "Default")
      (node (ref "R11") (pin "2") (pinfunction "2_2") (pintype "passive"))
      (node (ref "U1") (pin "25") (pinfunction "S6_25") (pintype "passive"))
    )
    (net (code "33") (name "/S7") (class "Default")
      (node (ref "R8") (pin "2") (pinfunction "2_2") (pintype "passive"))
      (node (ref "U1") (pin "23") (pinfunction "S7_23") (pintype "passive"))
    )
    (net (code "34") (name "/S11") (class "Default")
      (node (ref "R5") (pin "2") (pinfunction "2_2") (pintype "passive"))
      (node (ref "U1") (pin "13") (pinfunction "S11_13") (pintype "passive"))
    )
    (net (code "35") (name "/S12") (class "Default")
      (node (ref "R2") (pin "2") (pinfunction "2_2") (pintype "passive"))
      (node (ref "U1") (pin "11") (pinfunction "S12_11") (pintype "passive"))
    )
    (net (code "36") (name "/SCK") (class "Default")
      (node (ref "R34") (pin "1") (pinfunction "1_1") (pintype "passive"))
      (node (ref "U1") (pin "62") (pinfunction "SCK(IPA)_62") (pintype "passive"))
      (node (ref "XFMR") (pin "9") (pinfunction "9_9") (pintype "passive"))
    )
    (net (code "37") (name "/SDI") (class "Default")
      (node (ref "U1") (pin "53") (pinfunction "SDI(NC)_53") (pintype "passive"))
    )
    (net (code "38") (name "/SDO") (class "Default")
      (node (ref "U1") (pin "54") (pinfunction "SDO(NC)_54") (pintype "passive"))
    )
    (net (code "39") (name "/VREF1") (class "Default")
      (node (ref "C12") (pin "2") (pinfunction "2_2") (pintype "passive"))
      (node (ref "U1") (pin "51") (pinfunction "VREF1_51") (pintype "passive"))
    )
    (net (code "40") (name "/VREF2") (class "Default")
      (node (ref "C13") (pin "2") (pinfunction "2_2") (pintype "passive"))
      (node (ref "R41") (pin "1") (pinfunction "1_1") (pintype "passive"))
      (node (ref "R42") (pin "1") (pinfunction "1_1") (pintype "passive"))
      (node (ref "R43") (pin "1") (pinfunction "1_1") (pintype "passive"))
      (node (ref "R44") (pin "1") (pinfunction "1_1") (pintype "passive"))
      (node (ref "U1") (pin "50") (pinfunction "VREF2_50") (pintype "passive"))
    )
    (net (code "41") (name "/VREG") (class "Default")
      (node (ref "C11") (pin "2") (pinfunction "2_2") (pintype "passive"))
      (node (ref "Q9") (pin "1") (pinfunction "E_1") (pintype "passive"))
      (node (ref "S4") (pin "3") (pinfunction "3_3") (pintype "passive"))
      (node (ref "U1") (pin "48") (pinfunction "VREG_48") (pintype "passive"))
      (node (ref "U1") (pin "55") (pinfunction "ISOMD_55") (pintype "passive"))
    )
    (net (code "42") (name "/WDT") (class "Default")
      (node (ref "P12") (pin "9") (pinfunction "9_9") (pintype "passive"))
      (node (ref "U1") (pin "56") (pinfunction "WDT_56") (pintype "passive"))
    )
    (net (code "43") (name "GND") (class "Default")
      (node (ref "BT7") (pin "2") (pinfunction "-_2") (pintype "passive"))
      (node (ref "C10") (pin "1") (pinfunction "1_1") (pintype "passive"))
      (node (ref "C11") (pin "1") (pinfunction "1_1") (pintype "passive"))
      (node (ref "C12") (pin "1") (pinfunction "1_1") (pintype "passive"))
      (node (ref "C13") (pin "1") (pinfunction "1_1") (pintype "passive"))
      (node (ref "C14") (pin "1") (pinfunction "1_1") (pintype "passive"))
      (node (ref "C15") (pin "1") (pinfunction "1_1") (pintype "passive"))
      (node (ref "C7") (pin "1") (pinfunction "1_1") (pintype "passive"))
      (node (ref "C9") (pin "1") (pinfunction "1_1") (pintype "passive"))
      (node (ref "J4") (pin "1") (pinfunction "1_1") (pintype "passive"))
      (node (ref "P1") (pin "1") (pinfunction "1_1") (pintype "passive"))
      (node (ref "P1") (pin "3") (pinfunction "3_3") (pintype "passive"))
      (node (ref "P1") (pin "5") (pinfunction "5_5") (pintype "passive"))
      (node (ref "P1") (pin "7") (pinfunction "7_7") (pintype "passive"))
      (node (ref "P12") (pin "1") (pinfunction "1_1") (pintype "passive"))
      (node (ref "P5") (pin "2") (pinfunction "2_2") (pintype "passive"))
      (node (ref "P8") (pin "1") (pinfunction "1_1") (pintype "passive"))
      (node (ref "R21") (pin "2") (pinfunction "2_2") (pintype "passive"))
      (node (ref "R31") (pin "2") (pinfunction "2_2") (pintype "passive"))
      (node (ref "R51") (pin "1") (pinfunction "1_1") (pintype "passive"))
      (node (ref "S4") (pin "1") (pinfunction "1_1") (pintype "passive"))
      (node (ref "U1") (pin "38") (pinfunction "C0_38") (pintype "passive"))
      (node (ref "U1") (pin "59") (pinfunction "V-_59") (pintype "passive"))
      (node (ref "U1") (pin "60") (pinfunction "V-_60") (pintype "passive"))
      (node (ref "U1") (pin "65") (pinfunction "V-_65") (pintype "passive"))
    )
    (net (code "44") (name "Net-(C14-Pad2)") (class "Default")
      (node (ref "C14") (pin "2") (pinfunction "2_2") (pintype "passive"))
      (node (ref "R32") (pin "2") (pinfunction "2_2") (pintype "passive"))
      (node (ref "R33") (pin "1") (pinfunction "1_1") (pintype "passive"))
    )
    (net (code "45") (name "Net-(C15-Pad2)") (class "Default")
      (node (ref "C15") (pin "2") (pinfunction "2_2") (pintype "passive"))
      (node (ref "R34") (pin "2") (pinfunction "2_2") (pintype "passive"))
      (node (ref "R35") (pin "1") (pinfunction "1_1") (pintype "passive"))
    )
    (net (code "46") (name "Net-(D2-A)") (class "Default")
      (node (ref "D2") (pin "1") (pinfunction "A_1") (pintype "passive"))
      (node (ref "Q1") (pin "1") (pinfunction "D_1") (pintype "passive"))
      (node (ref "R3") (pin "1") (pinfunction "1_1") (pintype "passive"))
    )
    (net (code "47") (name "Net-(D2-K)") (class "Default")
      (node (ref "D2") (pin "2") (pinfunction "K_2") (pintype "passive"))
      (node (ref "R40") (pin "2") (pinfunction "2_2") (pintype "passive"))
    )
    (net (code "48") (name "Net-(D3-A)") (class "Default")
      (node (ref "D3") (pin "1") (pinfunction "A_1") (pintype "passive"))
      (node (ref "Q2") (pin "1") (pinfunction "D_1") (pintype "passive"))
      (node (ref "R6") (pin "1") (pinfunction "1_1") (pintype "passive"))
    )
    (net (code "49") (name "Net-(D3-K)") (class "Default")
      (node (ref "D3") (pin "2") (pinfunction "K_2") (pintype "passive"))
      (node (ref "R45") (pin "2") (pinfunction "2_2") (pintype "passive"))
    )
    (net (code "50") (name "Net-(D4-A)") (class "Default")
      (node (ref "D4") (pin "1") (pinfunction "A_1") (pintype "passive"))
      (node (ref "Q3") (pin "1") (pinfunction "D_1") (pintype "passive"))
      (node (ref "R9") (pin "1") (pinfunction "1_1") (pintype "passive"))
    )
    (net (code "51") (name "Net-(D4-K)") (class "Default")
      (node (ref "D4") (pin "2") (pinfunction "K_2") (pintype "passive"))
      (node (ref "R46") (pin "2") (pinfunction "2_2") (pintype "passive"))
    )
    (net (code "52") (name "Net-(D5-A)") (class "Default")
      (node (ref "D5") (pin "1") (pinfunction "A_1") (pintype "passive"))
      (node (ref "R22") (pin "2") (pinfunction "2_2") (pintype "passive"))
      (node (ref "S5") (pin "3") (pinfunction "3_3") (pintype "passive"))
    )
    (net (code "53") (name "Net-(D5-K)") (class "Default")
      (node (ref "D5") (pin "2") (pinfunction "K_2") (pintype "passive"))
      (node (ref "R23") (pin "1") (pinfunction "1_1") (pintype "passive"))
    )
    (net (code "54") (name "Net-(D6-A)") (class "Default")
      (node (ref "D6") (pin "1") (pinfunction "A_1") (pintype "passive"))
      (node (ref "Q4") (pin "1") (pinfunction "D_1") (pintype "passive"))
      (node (ref "R12") (pin "1") (pinfunction "1_1") (pintype "passive"))
    )
    (net (code "55") (name "Net-(D6-K)") (class "Default")
      (node (ref "D6") (pin "2") (pinfunction "K_2") (pintype "passive"))
      (node (ref "R48") (pin "2") (pinfunction "2_2") (pintype "passive"))
    )
    (net (code "56") (name "Net-(D7-A)") (class "Default")
      (node (ref "D7") (pin "1") (pinfunction "A_1") (pintype "passive"))
      (node (ref "Q5") (pin "1") (pinfunction "D_1") (pintype "passive"))
      (node (ref "R15") (pin "1") (pinfunction "1_1") (pintype "passive"))
    )
    (net (code "57") (name "Net-(D7-K)") (class "Default")
      (node (ref "D7") (pin "2") (pinfunction "K_2") (pintype "passive"))
      (node (ref "R49") (pin "2") (pinfunction "2_2") (pintype "passive"))
    )
    (net (code "58") (name "Net-(D8-A)") (class "Default")
      (node (ref "D8") (pin "1") (pinfunction "A_1") (pintype "passive"))
      (node (ref "Q6") (pin "1") (pinfunction "D_1") (pintype "passive"))
      (node (ref "R18") (pin "1") (pinfunction "1_1") (pintype "passive"))
    )
    (net (code "59") (name "Net-(D8-K)") (class "Default")
      (node (ref "D8") (pin "2") (pinfunction "K_2") (pintype "passive"))
      (node (ref "R50") (pin "2") (pinfunction "2_2") (pintype "passive"))
    )
    (net (code "60") (name "Net-(D9-A)") (class "Default")
      (node (ref "D9") (pin "1") (pinfunction "A_1") (pintype "passive"))
      (node (ref "Q7") (pin "1") (pinfunction "D_1") (pintype "passive"))
      (node (ref "R21") (pin "1") (pinfunction "1_1") (pintype "passive"))
    )
    (net (code "61") (name "Net-(D9-K)") (class "Default")
      (node (ref "D9") (pin "2") (pinfunction "K_2") (pintype "passive"))
      (node (ref "R51") (pin "2") (pinfunction "2_2") (pintype "passive"))
    )
    (net (code "62") (name "Net-(P5-Pad1)") (class "Default")
      (node (ref "P5") (pin "1") (pinfunction "1_1") (pintype "passive"))
      (node (ref "P9") (pin "2") (pinfunction "2_2") (pintype "passive"))
    )
    (net (code "63") (name "Net-(P8-Pad2)") (class "Default")
      (node (ref "P8") (pin "2") (pinfunction "2_2") (pintype "passive"))
      (node (ref "P9") (pin "1") (pinfunction "1_1") (pintype "passive"))
    )
    (net (code "64") (name "Net-(Q1-G)") (class "Default")
      (node (ref "Q1") (pin "2") (pinfunction "G_2") (pintype "passive"))
      (node (ref "R2") (pin "1") (pinfunction "1_1") (pintype "passive"))
    )
    (net (code "65") (name "Net-(Q2-G)") (class "Default")
      (node (ref "Q2") (pin "2") (pinfunction "G_2") (pintype "passive"))
      (node (ref "R5") (pin "1") (pinfunction "1_1") (pintype "passive"))
    )
    (net (code "66") (name "Net-(Q3-G)") (class "Default")
      (node (ref "Q3") (pin "2") (pinfunction "G_2") (pintype "passive"))
      (node (ref "R8") (pin "1") (pinfunction "1_1") (pintype "passive"))
    )
    (net (code "67") (name "Net-(Q4-G)") (class "Default")
      (node (ref "Q4") (pin "2") (pinfunction "G_2") (pintype "passive"))
      (node (ref "R11") (pin "1") (pinfunction "1_1") (pintype "passive"))
    )
    (net (code "68") (name "Net-(Q5-G)") (class "Default")
      (node (ref "Q5") (pin "2") (pinfunction "G_2") (pintype "passive"))
      (node (ref "R14") (pin "1") (pinfunction "1_1") (pintype "passive"))
    )
    (net (code "69") (name "Net-(Q6-G)") (class "Default")
      (node (ref "Q6") (pin "2") (pinfunction "G_2") (pintype "passive"))
      (node (ref "R17") (pin "1") (pinfunction "1_1") (pintype "passive"))
    )
    (net (code "70") (name "Net-(Q7-G)") (class "Default")
      (node (ref "Q7") (pin "2") (pinfunction "G_2") (pintype "passive"))
      (node (ref "R20") (pin "1") (pinfunction "1_1") (pintype "passive"))
    )
    (net (code "71") (name "Net-(Q9-C)") (class "Default")
      (node (ref "C10") (pin "2") (pinfunction "2_2") (pintype "passive"))
      (node (ref "Q9") (pin "3") (pinfunction "C_3") (pintype "passive"))
      (node (ref "R25") (pin "1") (pinfunction "1_1") (pintype "passive"))
    )
    (net (code "72") (name "Net-(U1-C4)") (class "Default")
      (node (ref "R27") (pin "2") (pinfunction "2_2") (pintype "passive"))
      (node (ref "U1") (pin "28") (pinfunction "C5_28") (pintype "passive"))
      (node (ref "U1") (pin "30") (pinfunction "C4_30") (pintype "passive"))
    )
    (net (code "73") (name "Net-(U1-C10)") (class "Default")
      (node (ref "R26") (pin "2") (pinfunction "2_2") (pintype "passive"))
      (node (ref "U1") (pin "16") (pinfunction "C10_16") (pintype "passive"))
      (node (ref "U1") (pin "18") (pinfunction "C9_18") (pintype "passive"))
      (node (ref "U1") (pin "20") (pinfunction "C8_20") (pintype "passive"))
    )
    (net (code "74") (name "Net-(U1-C13)") (class "Default")
      (node (ref "R24") (pin "2") (pinfunction "2_2") (pintype "passive"))
      (node (ref "U1") (pin "4") (pinfunction "C15_4") (pintype "passive"))
      (node (ref "U1") (pin "6") (pinfunction "C14_6") (pintype "passive"))
      (node (ref "U1") (pin "8") (pinfunction "C13_8") (pintype "passive"))
    )
    (net (code "75") (name "Net-(U1-DTEN)") (class "Default")
      (node (ref "S4") (pin "2") (pinfunction "2_2") (pintype "passive"))
      (node (ref "U1") (pin "52") (pinfunction "DTEN_52") (pintype "passive"))
    )
    (net (code "76") (name "Net-(U1-IBIAS)") (class "Default")
      (node (ref "R30") (pin "1") (pinfunction "1_1") (pintype "passive"))
      (node (ref "U1") (pin "57") (pinfunction "IBIAS_57") (pintype "passive"))
    )
    (net (code "77") (name "Net-(U1-ICMP)") (class "Default")
      (node (ref "R30") (pin "2") (pinfunction "2_2") (pintype "passive"))
      (node (ref "R31") (pin "1") (pinfunction "1_1") (pintype "passive"))
      (node (ref "U1") (pin "58") (pinfunction "ICMP_58") (pintype "passive"))
    )
    (net (code "78") (name "Net-(U1-IMB)") (class "Default")
      (node (ref "R33") (pin "2") (pinfunction "2_2") (pintype "passive"))
      (node (ref "U1") (pin "63") (pinfunction "IMB_63") (pintype "passive"))
      (node (ref "XFMR") (pin "7") (pinfunction "7_7") (pintype "passive"))
    )
    (net (code "79") (name "Net-(U1-IPB)") (class "Default")
      (node (ref "R32") (pin "1") (pinfunction "1_1") (pintype "passive"))
      (node (ref "U1") (pin "64") (pinfunction "IPB_64") (pintype "passive"))
      (node (ref "XFMR") (pin "6") (pinfunction "6_6") (pintype "passive"))
    )
    (net (code "80") (name "Net-(U1-V+)") (class "Default")
      (node (ref "C9") (pin "2") (pinfunction "2_2") (pintype "passive"))
      (node (ref "R22") (pin "1") (pinfunction "1_1") (pintype "passive"))
      (node (ref "U1") (pin "1") (pinfunction "V+_1") (pintype "passive"))
    )
    (net (code "81") (name "VCC") (class "Default")
      (node (ref "BT1") (pin "1") (pinfunction "+_1") (pintype "passive"))
      (node (ref "J5") (pin "1") (pinfunction "1_1") (pintype "passive"))
      (node (ref "P10") (pin "1") (pinfunction "1_1") (pintype "passive"))
      (node (ref "P10") (pin "2") (pinfunction "2_2") (pintype "passive"))
      (node (ref "P11") (pin "1") (pinfunction "1_1") (pintype "passive"))
      (node (ref "P11") (pin "2") (pinfunction "2_2") (pintype "passive"))
      (node (ref "P12") (pin "8") (pinfunction "8_8") (pintype "passive"))
      (node (ref "P6") (pin "1") (pinfunction "1_1") (pintype "passive"))
      (node (ref "P6") (pin "2") (pinfunction "2_2") (pintype "passive"))
      (node (ref "P7") (pin "1") (pinfunction "1_1") (pintype "passive"))
      (node (ref "P7") (pin "2") (pinfunction "2_2") (pintype "passive"))
      (node (ref "Q1") (pin "3") (pinfunction "S_3") (pintype "passive"))
      (node (ref "R1") (pin "1") (pinfunction "1_1") (pintype "passive"))
      (node (ref "R24") (pin "1") (pinfunction "1_1") (pintype "passive"))
      (node (ref "R25") (pin "2") (pinfunction "2_2") (pintype "passive"))
      (node (ref "S5") (pin "2") (pinfunction "2_2") (pintype "passive"))
    )
    (net (code "82") (name "unconnected-(S5-Pad1)") (class "Default")
      (node (ref "S5") (pin "1") (pinfunction "1_1") (pintype "passive+no_connect"))
    )
    (net (code "83") (name "unconnected-(U1-NC-Pad2)") (class "Default")
      (node (ref "U1") (pin "2") (pinfunction "NC_2") (pintype "passive+no_connect"))
    )
    (net (code "84") (name "unconnected-(U1-NC-Pad3)") (class "Default")
      (node (ref "U1") (pin "3") (pinfunction "NC_3") (pintype "passive+no_connect"))
    )
    (net (code "85") (name "unconnected-(U1-NC-Pad14)") (class "Default")
      (node (ref "U1") (pin "14") (pinfunction "NC_14") (pintype "passive+no_connect"))
    )
    (net (code "86") (name "unconnected-(U1-NC-Pad15)") (class "Default")
      (node (ref "U1") (pin "15") (pinfunction "NC_15") (pintype "passive+no_connect"))
    )
    (net (code "87") (name "unconnected-(U1-NC-Pad26)") (class "Default")
      (node (ref "U1") (pin "26") (pinfunction "NC_26") (pintype "passive+no_connect"))
    )
    (net (code "88") (name "unconnected-(U1-NC-Pad27)") (class "Default")
      (node (ref "U1") (pin "27") (pinfunction "NC_27") (pintype "passive+no_connect"))
    )
    (net (code "89") (name "unconnected-(U1-S4-Pad31)") (class "Default")
      (node (ref "U1") (pin "31") (pinfunction "S4_31") (pintype "passive+no_connect"))
    )
    (net (code "90") (name "unconnected-(U1-S5-Pad29)") (class "Default")
      (node (ref "U1") (pin "29") (pinfunction "S5_29") (pintype "passive+no_connect"))
    )
    (net (code "91") (name "unconnected-(U1-S8-Pad21)") (class "Default")
      (node (ref "U1") (pin "21") (pinfunction "S8_21") (pintype "passive"))
    )
    (net (code "92") (name "unconnected-(U1-S9-Pad19)") (class "Default")
      (node (ref "U1") (pin "19") (pinfunction "S9_19") (pintype "passive+no_connect"))
    )
    (net (code "93") (name "unconnected-(U1-S10-Pad17)") (class "Default")
      (node (ref "U1") (pin "17") (pinfunction "S10_17") (pintype "passive+no_connect"))
    )
    (net (code "94") (name "unconnected-(U1-S13-Pad9)") (class "Default")
      (node (ref "U1") (pin "9") (pinfunction "S13_9") (pintype "passive+no_connect"))
    )
    (net (code "95") (name "unconnected-(U1-S14-Pad7)") (class "Default")
      (node (ref "U1") (pin "7") (pinfunction "S14_7") (pintype "passive+no_connect"))
    )
    (net (code "96") (name "unconnected-(U1-S15-Pad5)") (class "Default")
      (node (ref "U1") (pin "5") (pinfunction "S15_5") (pintype "passive+no_connect"))
    )
    (net (code "97") (name "unconnected-(XFMR-Pad3)") (class "Default")
      (node (ref "XFMR") (pin "3") (pinfunction "3_3") (pintype "passive+no_connect"))
    )
    (net (code "98") (name "unconnected-(XFMR-Pad8)") (class "Default")
      (node (ref "XFMR") (pin "8") (pinfunction "8_8") (pintype "passive+no_connect"))
    )
  )
)
